# switch_blk.net
KiCad netlist of a schematic drawn in Altium Designer
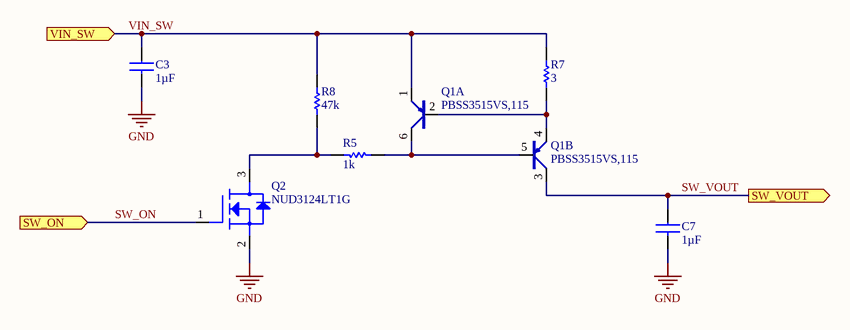
[diagram p0: switch_blk.SchDoc]

(export (version "E")
  (design (tool "Eeschema 10.0.6"))
  (components
    (comp (ref "C3")
      (value "1µF")
      (footprint "C0603")
      (description "CAP CER 1UF 16V X7R 0603")
      (fields (field (name "MPN") "EMK107B7105KA-T"))
      (libsource (lib "Capacitor") (part "EMK107B7105KA-T"))
    )
    (comp (ref "C7")
      (value "1µF")
      (footprint "C0603")
      (description "CAP CER 1UF 16V X7R 0603")
      (fields (field (name "MPN") "EMK107B7105KA-T"))
      (libsource (lib "Capacitor") (part "EMK107B7105KA-T"))
    )
    (comp (ref "Q1")
      (value "PBSS3515VS,115")
      (footprint "SOT50P160X60-6N")
      (description "TRANS 2PNP 15V 0.5A SOT666")
      (libsource (lib "") (part "PBSS3515VS,115_1"))
    )
    (comp (ref "Q2")
      (value "NUD3124LT1G")
      (footprint "SOT-23-3")
      (description "IC INDCT LOAD DRVR AUTO SOT23")
      (fields (field (name "MPN") "NUD3124LT1G"))
      (libsource (lib "Transistor") (part "NUD3124LT1G"))
    )
    (comp (ref "R5")
      (value "1k")
      (footprint "R0402")
      (description "RES SMD 1K OHM 1% 1/16W 0402")
      (fields (field (name "MPN") "CRCW04021K00FKED"))
      (libsource (lib "Res") (part "CRCW04021K00FKED"))
    )
    (comp (ref "R7")
      (value "3")
      (footprint "R0402")
      (description "RES 3 OHM 1% 1/16W 0402")
      (fields (field (name "MPN") "RC0402FR-073RL"))
      (libsource (lib "Res") (part "RC0402FR-073RL"))
    )
    (comp (ref "R8")
      (value "47k")
      (footprint "R0402")
      (description "RES SMD 47K OHM 5% 1/16W 0402")
      (fields (field (name "MPN") "RC0402JR-0747KL"))
      (libsource (lib "Res") (part "RC0402JR-0747KL"))
    )
  )
  (nets
    (net (code "1") (name "/SW_ON") (class "Default")
      (node (ref "Q2") (pin "1") (pinfunction "gate_1") (pintype "passive"))
    )
    (net (code "2") (name "/SW_VOUT") (class "Default")
      (node (ref "C7") (pin "1") (pinfunction "1_1") (pintype "passive"))
      (node (ref "Q1") (pin "3") (pinfunction "collector_3") (pintype "passive"))
    )
    (net (code "3") (name "/VIN_SW") (class "Default")
      (node (ref "C3") (pin "1") (pinfunction "1_1") (pintype "passive"))
      (node (ref "Q1") (pin "1") (pinfunction "emitter_1") (pintype "passive"))
      (node (ref "R7") (pin "2") (pinfunction "2_2") (pintype "passive"))
      (node (ref "R8") (pin "2") (pinfunction "2_2") (pintype "passive"))
    )
    (net (code "4") (name "GND") (class "Default")
      (node (ref "C3") (pin "2") (pinfunction "2_2") (pintype "passive"))
      (node (ref "C7") (pin "2") (pinfunction "2_2") (pintype "passive"))
      (node (ref "Q2") (pin "2") (pinfunction "source_2") (pintype "passive"))
    )
    (net (code "5") (name "Net-(Q1A-base)") (class "Default")
      (node (ref "Q1") (pin "2") (pinfunction "base_2") (pintype "passive"))
      (node (ref "Q1") (pin "4") (pinfunction "emitter_4") (pintype "passive"))
      (node (ref "R7") (pin "1") (pinfunction "1_1") (pintype "passive"))
    )
    (net (code "6") (name "Net-(Q1A-collector)") (class "Default")
      (node (ref "Q1") (pin "5") (pinfunction "base_5") (pintype "passive"))
      (node (ref "Q1") (pin "6") (pinfunction "collector_6") (pintype "passive"))
      (node (ref "R5") (pin "2") (pinfunction "2_2") (pintype "passive"))
    )
    (net (code "7") (name "Net-(Q2-drain)") (class "Default")
      (node (ref "Q2") (pin "3") (pinfunction "drain_3") (pintype "passive"))
      (node (ref "R5") (pin "1") (pinfunction "1_1") (pintype "passive"))
      (node (ref "R8") (pin "1") (pinfunction "1_1") (pintype "passive"))
    )
  )
)
